# hvreg_feedback.net
KiCad netlist of a schematic drawn in EAGLE
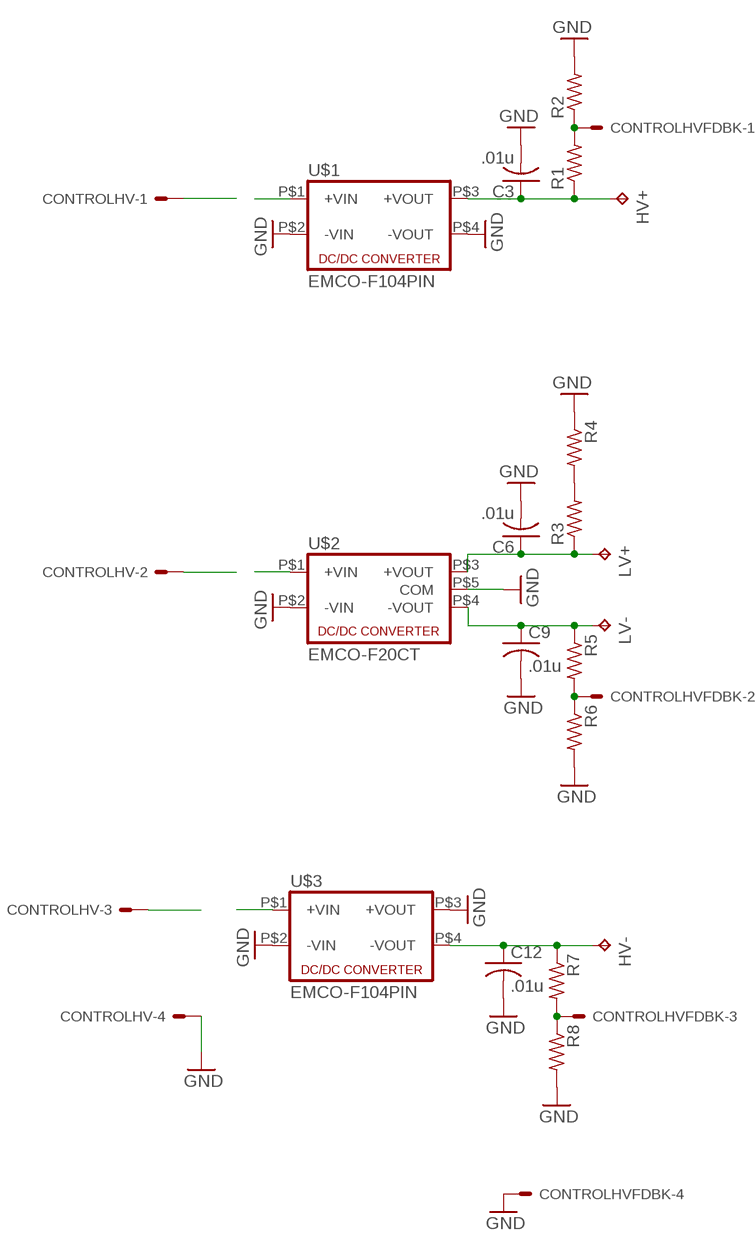
[diagram p0: schematic, sheet 1]

(export (version "E")
  (design (tool "Eeschema 10.0.6"))
  (components
    (comp (ref "C3")
      (value ".01u")
      (footprint "eagle-import:C075-042X103")
      (libsource (lib "eagle-import") (part "C-US075-042X103"))
    )
    (comp (ref "C6")
      (value ".01u")
      (footprint "eagle-import:C075-042X103")
      (libsource (lib "eagle-import") (part "C-US075-042X103"))
    )
    (comp (ref "C9")
      (value ".01u")
      (footprint "eagle-import:C075-042X103")
      (libsource (lib "eagle-import") (part "C-US075-042X103"))
    )
    (comp (ref "C12")
      (value ".01u")
      (footprint "eagle-import:C075-042X103")
      (libsource (lib "eagle-import") (part "C-US075-042X103"))
    )
    (comp (ref "CONTROLHV")
      (value "KK-156-4")
      (footprint "eagle-import:KK-156-4")
      (libsource (lib "eagle-import") (part "KK-156-4"))
    )
    (comp (ref "CONTROLHVFDBK")
      (value "KK-156-4")
      (footprint "eagle-import:KK-156-4")
      (libsource (lib "eagle-import") (part "KK-156-4"))
    )
    (comp (ref "HV+")
      (value "TPPAD1-20Y")
      (footprint "eagle-import:P1-20Y")
      (libsource (lib "eagle-import") (part "TPPAD1-20Y"))
    )
    (comp (ref "HV-")
      (value "TPPAD1-20Y")
      (footprint "eagle-import:P1-20Y")
      (libsource (lib "eagle-import") (part "TPPAD1-20Y"))
    )
    (comp (ref "LV+")
      (value "TPPAD1-20Y")
      (footprint "eagle-import:P1-20Y")
      (libsource (lib "eagle-import") (part "TPPAD1-20Y"))
    )
    (comp (ref "LV-")
      (value "TPPAD1-20Y")
      (footprint "eagle-import:P1-20Y")
      (libsource (lib "eagle-import") (part "TPPAD1-20Y"))
    )
    (comp (ref "R1")
      (value "R-US_0207/12")
      (footprint "eagle-import:0207_12")
      (libsource (lib "eagle-import") (part "R-US_0207/12"))
    )
    (comp (ref "R2")
      (value "R-US_0207/12")
      (footprint "eagle-import:0207_12")
      (libsource (lib "eagle-import") (part "R-US_0207/12"))
    )
    (comp (ref "R3")
      (value "R-US_0207/12")
      (footprint "eagle-import:0207_12")
      (libsource (lib "eagle-import") (part "R-US_0207/12"))
    )
    (comp (ref "R4")
      (value "R-US_0207/12")
      (footprint "eagle-import:0207_12")
      (libsource (lib "eagle-import") (part "R-US_0207/12"))
    )
    (comp (ref "R5")
      (value "R-US_0207/12")
      (footprint "eagle-import:0207_12")
      (libsource (lib "eagle-import") (part "R-US_0207/12"))
    )
    (comp (ref "R6")
      (value "R-US_0207/12")
      (footprint "eagle-import:0207_12")
      (libsource (lib "eagle-import") (part "R-US_0207/12"))
    )
    (comp (ref "R7")
      (value "R-US_0207/12")
      (footprint "eagle-import:0207_12")
      (libsource (lib "eagle-import") (part "R-US_0207/12"))
    )
    (comp (ref "R8")
      (value "R-US_0207/12")
      (footprint "eagle-import:0207_12")
      (libsource (lib "eagle-import") (part "R-US_0207/12"))
    )
    (comp (ref "U$1")
      (value "EMCO-F104PIN")
      (footprint "eagle-import:EMCO-F")
      (libsource (lib "eagle-import") (part "EMCO-F104PIN"))
    )
    (comp (ref "U$2")
      (value "EMCO-F20CT")
      (footprint "eagle-import:EMCO-F_CT")
      (libsource (lib "eagle-import") (part "EMCO-F20CT"))
    )
    (comp (ref "U$3")
      (value "EMCO-F104PIN")
      (footprint "eagle-import:EMCO-F")
      (libsource (lib "eagle-import") (part "EMCO-F104PIN"))
    )
  )
  (nets
    (net (code "1") (name "/VREG1") (class "Default")
      (node (ref "CONTROLHV") (pin "1") (pinfunction "S_1") (pintype "passive"))
      (node (ref "U$1") (pin "P$1") (pinfunction "+VIN_P$1") (pintype "passive"))
    )
    (net (code "2") (name "/VREG2") (class "Default")
      (node (ref "CONTROLHV") (pin "2") (pinfunction "S_2") (pintype "passive"))
      (node (ref "U$2") (pin "P$1") (pinfunction "+VIN_P$1") (pintype "passive"))
    )
    (net (code "3") (name "/VREG3") (class "Default")
      (node (ref "CONTROLHV") (pin "3") (pinfunction "S_3") (pintype "passive"))
      (node (ref "U$3") (pin "P$1") (pinfunction "+VIN_P$1") (pintype "passive"))
    )
    (net (code "4") (name "GND") (class "Default")
      (node (ref "C12") (pin "2") (pinfunction "2_2") (pintype "passive"))
      (node (ref "C3") (pin "2") (pinfunction "2_2") (pintype "passive"))
      (node (ref "C6") (pin "2") (pinfunction "2_2") (pintype "passive"))
      (node (ref "C9") (pin "2") (pinfunction "2_2") (pintype "passive"))
      (node (ref "CONTROLHV") (pin "4") (pinfunction "S_4") (pintype "passive"))
      (node (ref "CONTROLHVFDBK") (pin "4") (pinfunction "S_4") (pintype "passive"))
      (node (ref "R2") (pin "2") (pinfunction "2_2") (pintype "passive"))
      (node (ref "R4") (pin "1") (pinfunction "1_1") (pintype "passive"))
      (node (ref "R6") (pin "2") (pinfunction "2_2") (pintype "passive"))
      (node (ref "R8") (pin "2") (pinfunction "2_2") (pintype "passive"))
      (node (ref "U$1") (pin "P$2") (pinfunction "-VIN_P$2") (pintype "passive"))
      (node (ref "U$1") (pin "P$4") (pinfunction "-VOUT_P$4") (pintype "passive"))
      (node (ref "U$2") (pin "P$2") (pinfunction "-VIN_P$2") (pintype "passive"))
      (node (ref "U$2") (pin "P$5") (pinfunction "COM_P$5") (pintype "passive"))
      (node (ref "U$3") (pin "P$2") (pinfunction "-VIN_P$2") (pintype "passive"))
      (node (ref "U$3") (pin "P$3") (pinfunction "+VOUT_P$3") (pintype "passive"))
    )
    (net (code "5") (name "Net-(CONTROLHVFDBKA-S)") (class "Default")
      (node (ref "CONTROLHVFDBK") (pin "1") (pinfunction "S_1") (pintype "passive"))
      (node (ref "R1") (pin "2") (pinfunction "2_2") (pintype "passive"))
      (node (ref "R2") (pin "1") (pinfunction "1_1") (pintype "passive"))
    )
    (net (code "6") (name "Net-(CONTROLHVFDBKB-S)") (class "Default")
      (node (ref "CONTROLHVFDBK") (pin "2") (pinfunction "S_2") (pintype "passive"))
      (node (ref "R5") (pin "2") (pinfunction "2_2") (pintype "passive"))
      (node (ref "R6") (pin "1") (pinfunction "1_1") (pintype "passive"))
    )
    (net (code "7") (name "Net-(CONTROLHVFDBKC-S)") (class "Default")
      (node (ref "CONTROLHVFDBK") (pin "3") (pinfunction "S_3") (pintype "passive"))
      (node (ref "R7") (pin "2") (pinfunction "2_2") (pintype "passive"))
      (node (ref "R8") (pin "1") (pinfunction "1_1") (pintype "passive"))
    )
    (net (code "8") (name "Net-(R3-Pad2)") (class "Default")
      (node (ref "R3") (pin "2") (pinfunction "2_2") (pintype "passive"))
      (node (ref "R4") (pin "2") (pinfunction "2_2") (pintype "passive"))
    )
    (net (code "9") (name "Net-(U$1-+VOUT)") (class "Default")
      (node (ref "C3") (pin "1") (pinfunction "1_1") (pintype "passive"))
      (node (ref "HV+") (pin "TP") (pinfunction "TP_TP") (pintype "input"))
      (node (ref "R1") (pin "1") (pinfunction "1_1") (pintype "passive"))
      (node (ref "U$1") (pin "P$3") (pinfunction "+VOUT_P$3") (pintype "passive"))
    )
    (net (code "10") (name "Net-(U$2-+VOUT)") (class "Default")
      (node (ref "C6") (pin "1") (pinfunction "1_1") (pintype "passive"))
      (node (ref "LV+") (pin "TP") (pinfunction "TP_TP") (pintype "input"))
      (node (ref "R3") (pin "1") (pinfunction "1_1") (pintype "passive"))
      (node (ref "U$2") (pin "P$3") (pinfunction "+VOUT_P$3") (pintype "passive"))
    )
    (net (code "11") (name "Net-(U$2--VOUT)") (class "Default")
      (node (ref "C9") (pin "1") (pinfunction "1_1") (pintype "passive"))
      (node (ref "LV-") (pin "TP") (pinfunction "TP_TP") (pintype "input"))
      (node (ref "R5") (pin "1") (pinfunction "1_1") (pintype "passive"))
      (node (ref "U$2") (pin "P$4") (pinfunction "-VOUT_P$4") (pintype "passive"))
    )
    (net (code "12") (name "Net-(U$3--VOUT)") (class "Default")
      (node (ref "C12") (pin "1") (pinfunction "1_1") (pintype "passive"))
      (node (ref "HV-") (pin "TP") (pinfunction "TP_TP") (pintype "input"))
      (node (ref "R7") (pin "1") (pinfunction "1_1") (pintype "passive"))
      (node (ref "U$3") (pin "P$4") (pinfunction "-VOUT_P$4") (pintype "passive"))
    )
  )
)
